# MCORD_MCX_SAS.net
KiCad netlist of a schematic drawn in Altium Designer
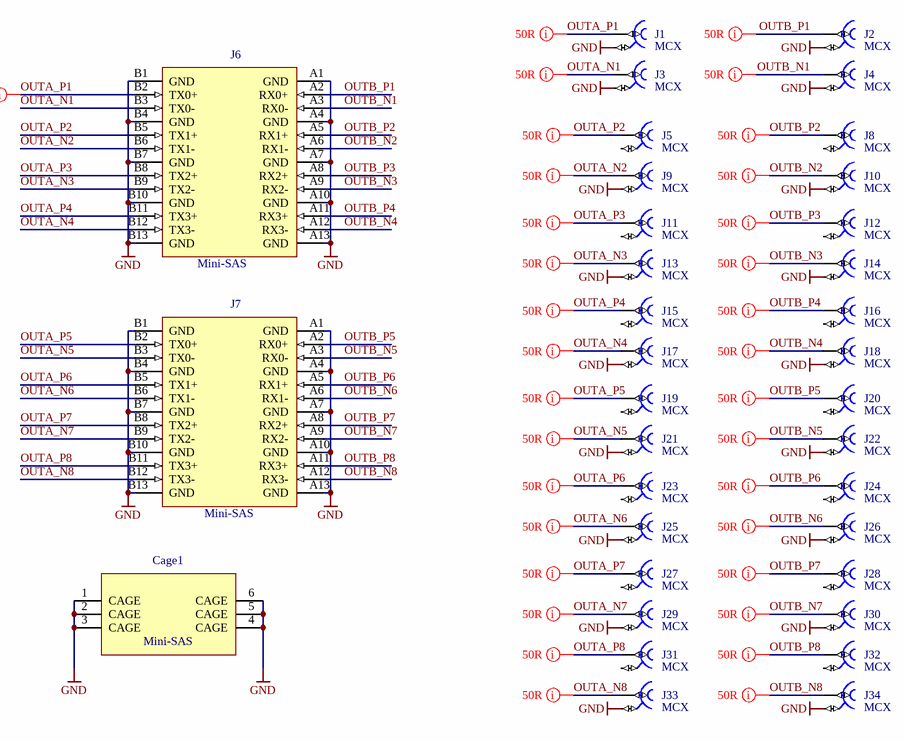
[diagram p0: MCORD_MCX_SAS.SchDoc]

(export (version "E")
  (design (tool "Eeschema 10.0.6"))
  (components
    (comp (ref "Cage1")
      (value "Mini-SAS")
      (footprint "TYCO_1888321-2")
      (description "Mini-SAS Cage (6Pins)")
      (fields
        (field (name "PART NUMBER") "TYCO_1888321-2")
        (field (name "MANUFACTURER") "TYCO ELECTRONICS")
        (field (name "AUTHOR") "CERN DEM BC")
      )
      (libsource (lib "Connectors") (part "Mini-SAS Cage (6Pins)"))
    )
    (comp (ref "J1")
      (value "MCX")
      (footprint "AMPHENOL_919-383J-51A")
      (fields
        (field (name "PART NUMBER") "AMPHENOL_919-383J-51A")
        (field (name "FAMILY") "MCX")
        (field (name "MANUFACTURER") "AMPHENOL")
        (field (name "MANUFACTURER PART NUMBER") "919-383J-51A")
        (field (name "AUTHOR") "CERN DEM BC")
      )
      (libsource (lib "Connectors") (part "Coax_1Female_1Shield"))
    )
    (comp (ref "J2")
      (value "MCX")
      (footprint "AMPHENOL_919-383J-51A")
      (fields
        (field (name "PART NUMBER") "AMPHENOL_919-383J-51A")
        (field (name "FAMILY") "MCX")
        (field (name "MANUFACTURER") "AMPHENOL")
        (field (name "MANUFACTURER PART NUMBER") "919-383J-51A")
        (field (name "AUTHOR") "CERN DEM BC")
      )
      (libsource (lib "Connectors") (part "Coax_1Female_1Shield"))
    )
    (comp (ref "J3")
      (value "MCX")
      (footprint "AMPHENOL_919-383J-51A")
      (fields
        (field (name "PART NUMBER") "AMPHENOL_919-383J-51A")
        (field (name "FAMILY") "MCX")
        (field (name "MANUFACTURER") "AMPHENOL")
        (field (name "MANUFACTURER PART NUMBER") "919-383J-51A")
        (field (name "AUTHOR") "CERN DEM BC")
      )
      (libsource (lib "Connectors") (part "Coax_1Female_1Shield"))
    )
    (comp (ref "J4")
      (value "MCX")
      (footprint "AMPHENOL_919-383J-51A")
      (fields
        (field (name "PART NUMBER") "AMPHENOL_919-383J-51A")
        (field (name "FAMILY") "MCX")
        (field (name "MANUFACTURER") "AMPHENOL")
        (field (name "MANUFACTURER PART NUMBER") "919-383J-51A")
        (field (name "AUTHOR") "CERN DEM BC")
      )
      (libsource (lib "Connectors") (part "Coax_1Female_1Shield"))
    )
    (comp (ref "J5")
      (value "MCX")
      (footprint "AMPHENOL_919-383J-51A")
      (fields
        (field (name "PART NUMBER") "AMPHENOL_919-383J-51A")
        (field (name "FAMILY") "MCX")
        (field (name "MANUFACTURER") "AMPHENOL")
        (field (name "MANUFACTURER PART NUMBER") "919-383J-51A")
        (field (name "AUTHOR") "CERN DEM BC")
      )
      (libsource (lib "Connectors") (part "Coax_1Female_1Shield"))
    )
    (comp (ref "J6")
      (value "Mini-SAS")
      (footprint "TYCO_1761987-7")
      (description "26 Position Mini-Sas Connector (Quad Small Form-Factor SFF-8088)")
      (fields
        (field (name "PART NUMBER") "TYCO_1761987-7")
        (field (name "MANUFACTURER") "TYCO ELECTRONICS")
        (field (name "AUTHOR") "CERN DEM MR")
      )
      (libsource (lib "Connectors") (part "Mini-SAS"))
    )
    (comp (ref "J7")
      (value "Mini-SAS")
      (footprint "TYCO_1761987-7")
      (description "26 Position Mini-Sas Connector (Quad Small Form-Factor SFF-8088)")
      (fields
        (field (name "PART NUMBER") "TYCO_1761987-7")
        (field (name "MANUFACTURER") "TYCO ELECTRONICS")
        (field (name "AUTHOR") "CERN DEM MR")
      )
      (libsource (lib "Connectors") (part "Mini-SAS"))
    )
    (comp (ref "J8")
      (value "MCX")
      (footprint "AMPHENOL_919-383J-51A")
      (fields
        (field (name "PART NUMBER") "AMPHENOL_919-383J-51A")
        (field (name "FAMILY") "MCX")
        (field (name "MANUFACTURER") "AMPHENOL")
        (field (name "MANUFACTURER PART NUMBER") "919-383J-51A")
        (field (name "AUTHOR") "CERN DEM BC")
      )
      (libsource (lib "Connectors") (part "Coax_1Female_1Shield"))
    )
    (comp (ref "J9")
      (value "MCX")
      (footprint "AMPHENOL_919-383J-51A")
      (fields
        (field (name "PART NUMBER") "AMPHENOL_919-383J-51A")
        (field (name "FAMILY") "MCX")
        (field (name "MANUFACTURER") "AMPHENOL")
        (field (name "MANUFACTURER PART NUMBER") "919-383J-51A")
        (field (name "AUTHOR") "CERN DEM BC")
      )
      (libsource (lib "Connectors") (part "Coax_1Female_1Shield"))
    )
    (comp (ref "J10")
      (value "MCX")
      (footprint "AMPHENOL_919-383J-51A")
      (fields
        (field (name "PART NUMBER") "AMPHENOL_919-383J-51A")
        (field (name "FAMILY") "MCX")
        (field (name "MANUFACTURER") "AMPHENOL")
        (field (name "MANUFACTURER PART NUMBER") "919-383J-51A")
        (field (name "AUTHOR") "CERN DEM BC")
      )
      (libsource (lib "Connectors") (part "Coax_1Female_1Shield"))
    )
    (comp (ref "J11")
      (value "MCX")
      (footprint "AMPHENOL_919-383J-51A")
      (fields
        (field (name "PART NUMBER") "AMPHENOL_919-383J-51A")
        (field (name "FAMILY") "MCX")
        (field (name "MANUFACTURER") "AMPHENOL")
        (field (name "MANUFACTURER PART NUMBER") "919-383J-51A")
        (field (name "AUTHOR") "CERN DEM BC")
      )
      (libsource (lib "Connectors") (part "Coax_1Female_1Shield"))
    )
    (comp (ref "J12")
      (value "MCX")
      (footprint "AMPHENOL_919-383J-51A")
      (fields
        (field (name "PART NUMBER") "AMPHENOL_919-383J-51A")
        (field (name "FAMILY") "MCX")
        (field (name "MANUFACTURER") "AMPHENOL")
        (field (name "MANUFACTURER PART NUMBER") "919-383J-51A")
        (field (name "AUTHOR") "CERN DEM BC")
      )
      (libsource (lib "Connectors") (part "Coax_1Female_1Shield"))
    )
    (comp (ref "J13")
      (value "MCX")
      (footprint "AMPHENOL_919-383J-51A")
      (fields
        (field (name "PART NUMBER") "AMPHENOL_919-383J-51A")
        (field (name "FAMILY") "MCX")
        (field (name "MANUFACTURER") "AMPHENOL")
        (field (name "MANUFACTURER PART NUMBER") "919-383J-51A")
        (field (name "AUTHOR") "CERN DEM BC")
      )
      (libsource (lib "Connectors") (part "Coax_1Female_1Shield"))
    )
    (comp (ref "J14")
      (value "MCX")
      (footprint "AMPHENOL_919-383J-51A")
      (fields
        (field (name "PART NUMBER") "AMPHENOL_919-383J-51A")
        (field (name "FAMILY") "MCX")
        (field (name "MANUFACTURER") "AMPHENOL")
        (field (name "MANUFACTURER PART NUMBER") "919-383J-51A")
        (field (name "AUTHOR") "CERN DEM BC")
      )
      (libsource (lib "Connectors") (part "Coax_1Female_1Shield"))
    )
    (comp (ref "J15")
      (value "MCX")
      (footprint "AMPHENOL_919-383J-51A")
      (fields
        (field (name "PART NUMBER") "AMPHENOL_919-383J-51A")
        (field (name "FAMILY") "MCX")
        (field (name "MANUFACTURER") "AMPHENOL")
        (field (name "MANUFACTURER PART NUMBER") "919-383J-51A")
        (field (name "AUTHOR") "CERN DEM BC")
      )
      (libsource (lib "Connectors") (part "Coax_1Female_1Shield"))
    )
    (comp (ref "J16")
      (value "MCX")
      (footprint "AMPHENOL_919-383J-51A")
      (fields
        (field (name "PART NUMBER") "AMPHENOL_919-383J-51A")
        (field (name "FAMILY") "MCX")
        (field (name "MANUFACTURER") "AMPHENOL")
        (field (name "MANUFACTURER PART NUMBER") "919-383J-51A")
        (field (name "AUTHOR") "CERN DEM BC")
      )
      (libsource (lib "Connectors") (part "Coax_1Female_1Shield"))
    )
    (comp (ref "J17")
      (value "MCX")
      (footprint "AMPHENOL_919-383J-51A")
      (fields
        (field (name "PART NUMBER") "AMPHENOL_919-383J-51A")
        (field (name "FAMILY") "MCX")
        (field (name "MANUFACTURER") "AMPHENOL")
        (field (name "MANUFACTURER PART NUMBER") "919-383J-51A")
        (field (name "AUTHOR") "CERN DEM BC")
      )
      (libsource (lib "Connectors") (part "Coax_1Female_1Shield"))
    )
    (comp (ref "J18")
      (value "MCX")
      (footprint "AMPHENOL_919-383J-51A")
      (fields
        (field (name "PART NUMBER") "AMPHENOL_919-383J-51A")
        (field (name "FAMILY") "MCX")
        (field (name "MANUFACTURER") "AMPHENOL")
        (field (name "MANUFACTURER PART NUMBER") "919-383J-51A")
        (field (name "AUTHOR") "CERN DEM BC")
      )
      (libsource (lib "Connectors") (part "Coax_1Female_1Shield"))
    )
    (comp (ref "J19")
      (value "MCX")
      (footprint "AMPHENOL_919-383J-51A")
      (fields
        (field (name "PART NUMBER") "AMPHENOL_919-383J-51A")
        (field (name "FAMILY") "MCX")
        (field (name "MANUFACTURER") "AMPHENOL")
        (field (name "MANUFACTURER PART NUMBER") "919-383J-51A")
        (field (name "AUTHOR") "CERN DEM BC")
      )
      (libsource (lib "Connectors") (part "Coax_1Female_1Shield"))
    )
    (comp (ref "J20")
      (value "MCX")
      (footprint "AMPHENOL_919-383J-51A")
      (fields
        (field (name "PART NUMBER") "AMPHENOL_919-383J-51A")
        (field (name "FAMILY") "MCX")
        (field (name "MANUFACTURER") "AMPHENOL")
        (field (name "MANUFACTURER PART NUMBER") "919-383J-51A")
        (field (name "AUTHOR") "CERN DEM BC")
      )
      (libsource (lib "Connectors") (part "Coax_1Female_1Shield"))
    )
    (comp (ref "J21")
      (value "MCX")
      (footprint "AMPHENOL_919-383J-51A")
      (fields
        (field (name "PART NUMBER") "AMPHENOL_919-383J-51A")
        (field (name "FAMILY") "MCX")
        (field (name "MANUFACTURER") "AMPHENOL")
        (field (name "MANUFACTURER PART NUMBER") "919-383J-51A")
        (field (name "AUTHOR") "CERN DEM BC")
      )
      (libsource (lib "Connectors") (part "Coax_1Female_1Shield"))
    )
    (comp (ref "J22")
      (value "MCX")
      (footprint "AMPHENOL_919-383J-51A")
      (fields
        (field (name "PART NUMBER") "AMPHENOL_919-383J-51A")
        (field (name "FAMILY") "MCX")
        (field (name "MANUFACTURER") "AMPHENOL")
        (field (name "MANUFACTURER PART NUMBER") "919-383J-51A")
        (field (name "AUTHOR") "CERN DEM BC")
      )
      (libsource (lib "Connectors") (part "Coax_1Female_1Shield"))
    )
    (comp (ref "J23")
      (value "MCX")
      (footprint "AMPHENOL_919-383J-51A")
      (fields
        (field (name "PART NUMBER") "AMPHENOL_919-383J-51A")
        (field (name "FAMILY") "MCX")
        (field (name "MANUFACTURER") "AMPHENOL")
        (field (name "MANUFACTURER PART NUMBER") "919-383J-51A")
        (field (name "AUTHOR") "CERN DEM BC")
      )
      (libsource (lib "Connectors") (part "Coax_1Female_1Shield"))
    )
    (comp (ref "J24")
      (value "MCX")
      (footprint "AMPHENOL_919-383J-51A")
      (fields
        (field (name "PART NUMBER") "AMPHENOL_919-383J-51A")
        (field (name "FAMILY") "MCX")
        (field (name "MANUFACTURER") "AMPHENOL")
        (field (name "MANUFACTURER PART NUMBER") "919-383J-51A")
        (field (name "AUTHOR") "CERN DEM BC")
      )
      (libsource (lib "Connectors") (part "Coax_1Female_1Shield"))
    )
    (comp (ref "J25")
      (value "MCX")
      (footprint "AMPHENOL_919-383J-51A")
      (fields
        (field (name "PART NUMBER") "AMPHENOL_919-383J-51A")
        (field (name "FAMILY") "MCX")
        (field (name "MANUFACTURER") "AMPHENOL")
        (field (name "MANUFACTURER PART NUMBER") "919-383J-51A")
        (field (name "AUTHOR") "CERN DEM BC")
      )
      (libsource (lib "Connectors") (part "Coax_1Female_1Shield"))
    )
    (comp (ref "J26")
      (value "MCX")
      (footprint "AMPHENOL_919-383J-51A")
      (fields
        (field (name "PART NUMBER") "AMPHENOL_919-383J-51A")
        (field (name "FAMILY") "MCX")
        (field (name "MANUFACTURER") "AMPHENOL")
        (field (name "MANUFACTURER PART NUMBER") "919-383J-51A")
        (field (name "AUTHOR") "CERN DEM BC")
      )
      (libsource (lib "Connectors") (part "Coax_1Female_1Shield"))
    )
    (comp (ref "J27")
      (value "MCX")
      (footprint "AMPHENOL_919-383J-51A")
      (fields
        (field (name "PART NUMBER") "AMPHENOL_919-383J-51A")
        (field (name "FAMILY") "MCX")
        (field (name "MANUFACTURER") "AMPHENOL")
        (field (name "MANUFACTURER PART NUMBER") "919-383J-51A")
        (field (name "AUTHOR") "CERN DEM BC")
      )
      (libsource (lib "Connectors") (part "Coax_1Female_1Shield"))
    )
    (comp (ref "J28")
      (value "MCX")
      (footprint "AMPHENOL_919-383J-51A")
      (fields
        (field (name "PART NUMBER") "AMPHENOL_919-383J-51A")
        (field (name "FAMILY") "MCX")
        (field (name "MANUFACTURER") "AMPHENOL")
        (field (name "MANUFACTURER PART NUMBER") "919-383J-51A")
        (field (name "AUTHOR") "CERN DEM BC")
      )
      (libsource (lib "Connectors") (part "Coax_1Female_1Shield"))
    )
    (comp (ref "J29")
      (value "MCX")
      (footprint "AMPHENOL_919-383J-51A")
      (fields
        (field (name "PART NUMBER") "AMPHENOL_919-383J-51A")
        (field (name "FAMILY") "MCX")
        (field (name "MANUFACTURER") "AMPHENOL")
        (field (name "MANUFACTURER PART NUMBER") "919-383J-51A")
        (field (name "AUTHOR") "CERN DEM BC")
      )
      (libsource (lib "Connectors") (part "Coax_1Female_1Shield"))
    )
    (comp (ref "J30")
      (value "MCX")
      (footprint "AMPHENOL_919-383J-51A")
      (fields
        (field (name "PART NUMBER") "AMPHENOL_919-383J-51A")
        (field (name "FAMILY") "MCX")
        (field (name "MANUFACTURER") "AMPHENOL")
        (field (name "MANUFACTURER PART NUMBER") "919-383J-51A")
        (field (name "AUTHOR") "CERN DEM BC")
      )
      (libsource (lib "Connectors") (part "Coax_1Female_1Shield"))
    )
    (comp (ref "J31")
      (value "MCX")
      (footprint "AMPHENOL_919-383J-51A")
      (fields
        (field (name "PART NUMBER") "AMPHENOL_919-383J-51A")
        (field (name "FAMILY") "MCX")
        (field (name "MANUFACTURER") "AMPHENOL")
        (field (name "MANUFACTURER PART NUMBER") "919-383J-51A")
        (field (name "AUTHOR") "CERN DEM BC")
      )
      (libsource (lib "Connectors") (part "Coax_1Female_1Shield"))
    )
    (comp (ref "J32")
      (value "MCX")
      (footprint "AMPHENOL_919-383J-51A")
      (fields
        (field (name "PART NUMBER") "AMPHENOL_919-383J-51A")
        (field (name "FAMILY") "MCX")
        (field (name "MANUFACTURER") "AMPHENOL")
        (field (name "MANUFACTURER PART NUMBER") "919-383J-51A")
        (field (name "AUTHOR") "CERN DEM BC")
      )
      (libsource (lib "Connectors") (part "Coax_1Female_1Shield"))
    )
    (comp (ref "J33")
      (value "MCX")
      (footprint "AMPHENOL_919-383J-51A")
      (fields
        (field (name "PART NUMBER") "AMPHENOL_919-383J-51A")
        (field (name "FAMILY") "MCX")
        (field (name "MANUFACTURER") "AMPHENOL")
        (field (name "MANUFACTURER PART NUMBER") "919-383J-51A")
        (field (name "AUTHOR") "CERN DEM BC")
      )
      (libsource (lib "Connectors") (part "Coax_1Female_1Shield"))
    )
    (comp (ref "J34")
      (value "MCX")
      (footprint "AMPHENOL_919-383J-51A")
      (fields
        (field (name "PART NUMBER") "AMPHENOL_919-383J-51A")
        (field (name "FAMILY") "MCX")
        (field (name "MANUFACTURER") "AMPHENOL")
        (field (name "MANUFACTURER PART NUMBER") "919-383J-51A")
        (field (name "AUTHOR") "CERN DEM BC")
      )
      (libsource (lib "Connectors") (part "Coax_1Female_1Shield"))
    )
  )
  (nets
    (net (code "1") (name "/OUTA_N1") (class "Default")
      (node (ref "J3") (pin "1") (pinfunction "1_1") (pintype "bidirectional"))
      (node (ref "J6") (pin "B3") (pinfunction "TX0-_B3") (pintype "input"))
    )
    (net (code "2") (name "/OUTA_N2") (class "Default")
      (node (ref "J6") (pin "B6") (pinfunction "TX1-_B6") (pintype "input"))
      (node (ref "J9") (pin "1") (pinfunction "1_1") (pintype "bidirectional"))
    )
    (net (code "3") (name "/OUTA_N3") (class "Default")
      (node (ref "J13") (pin "1") (pinfunction "1_1") (pintype "bidirectional"))
      (node (ref "J6") (pin "B9") (pinfunction "TX2-_B9") (pintype "input"))
    )
    (net (code "4") (name "/OUTA_N4") (class "Default")
      (node (ref "J17") (pin "1") (pinfunction "1_1") (pintype "bidirectional"))
      (node (ref "J6") (pin "B12") (pinfunction "TX3-_B12") (pintype "input"))
    )
    (net (code "5") (name "/OUTA_N5") (class "Default")
      (node (ref "J21") (pin "1") (pinfunction "1_1") (pintype "bidirectional"))
      (node (ref "J7") (pin "B3") (pinfunction "TX0-_B3") (pintype "input"))
    )
    (net (code "6") (name "/OUTA_N6") (class "Default")
      (node (ref "J25") (pin "1") (pinfunction "1_1") (pintype "bidirectional"))
      (node (ref "J7") (pin "B6") (pinfunction "TX1-_B6") (pintype "input"))
    )
    (net (code "7") (name "/OUTA_N7") (class "Default")
      (node (ref "J29") (pin "1") (pinfunction "1_1") (pintype "bidirectional"))
      (node (ref "J7") (pin "B9") (pinfunction "TX2-_B9") (pintype "input"))
    )
    (net (code "8") (name "/OUTA_N8") (class "Default")
      (node (ref "J33") (pin "1") (pinfunction "1_1") (pintype "bidirectional"))
      (node (ref "J7") (pin "B12") (pinfunction "TX3-_B12") (pintype "input"))
    )
    (net (code "9") (name "/OUTA_P1") (class "Default")
      (node (ref "J1") (pin "1") (pinfunction "1_1") (pintype "bidirectional"))
      (node (ref "J6") (pin "B2") (pinfunction "TX0+_B2") (pintype "input"))
    )
    (net (code "10") (name "/OUTA_P2") (class "Default")
      (node (ref "J5") (pin "1") (pinfunction "1_1") (pintype "bidirectional"))
      (node (ref "J6") (pin "B5") (pinfunction "TX1+_B5") (pintype "input"))
    )
    (net (code "11") (name "/OUTA_P3") (class "Default")
      (node (ref "J11") (pin "1") (pinfunction "1_1") (pintype "bidirectional"))
      (node (ref "J6") (pin "B8") (pinfunction "TX2+_B8") (pintype "input"))
    )
    (net (code "12") (name "/OUTA_P4") (class "Default")
      (node (ref "J15") (pin "1") (pinfunction "1_1") (pintype "bidirectional"))
      (node (ref "J6") (pin "B11") (pinfunction "TX3+_B11") (pintype "input"))
    )
    (net (code "13") (name "/OUTA_P5") (class "Default")
      (node (ref "J19") (pin "1") (pinfunction "1_1") (pintype "bidirectional"))
      (node (ref "J7") (pin "B2") (pinfunction "TX0+_B2") (pintype "input"))
    )
    (net (code "14") (name "/OUTA_P6") (class "Default")
      (node (ref "J23") (pin "1") (pinfunction "1_1") (pintype "bidirectional"))
      (node (ref "J7") (pin "B5") (pinfunction "TX1+_B5") (pintype "input"))
    )
    (net (code "15") (name "/OUTA_P7") (class "Default")
      (node (ref "J27") (pin "1") (pinfunction "1_1") (pintype "bidirectional"))
      (node (ref "J7") (pin "B8") (pinfunction "TX2+_B8") (pintype "input"))
    )
    (net (code "16") (name "/OUTA_P8") (class "Default")
      (node (ref "J31") (pin "1") (pinfunction "1_1") (pintype "bidirectional"))
      (node (ref "J7") (pin "B11") (pinfunction "TX3+_B11") (pintype "input"))
    )
    (net (code "17") (name "/OUTB_N1") (class "Default")
      (node (ref "J4") (pin "1") (pinfunction "1_1") (pintype "bidirectional"))
      (node (ref "J6") (pin "A3") (pinfunction "RX0-_A3") (pintype "input"))
    )
    (net (code "18") (name "/OUTB_N2") (class "Default")
      (node (ref "J10") (pin "1") (pinfunction "1_1") (pintype "bidirectional"))
      (node (ref "J6") (pin "A6") (pinfunction "RX1-_A6") (pintype "input"))
    )
    (net (code "19") (name "/OUTB_N3") (class "Default")
      (node (ref "J14") (pin "1") (pinfunction "1_1") (pintype "bidirectional"))
      (node (ref "J6") (pin "A9") (pinfunction "RX2-_A9") (pintype "input"))
    )
    (net (code "20") (name "/OUTB_N4") (class "Default")
      (node (ref "J18") (pin "1") (pinfunction "1_1") (pintype "bidirectional"))
      (node (ref "J6") (pin "A12") (pinfunction "RX3-_A12") (pintype "input"))
    )
    (net (code "21") (name "/OUTB_N5") (class "Default")
      (node (ref "J22") (pin "1") (pinfunction "1_1") (pintype "bidirectional"))
      (node (ref "J7") (pin "A3") (pinfunction "RX0-_A3") (pintype "input"))
    )
    (net (code "22") (name "/OUTB_N6") (class "Default")
      (node (ref "J26") (pin "1") (pinfunction "1_1") (pintype "bidirectional"))
      (node (ref "J7") (pin "A6") (pinfunction "RX1-_A6") (pintype "input"))
    )
    (net (code "23") (name "/OUTB_N7") (class "Default")
      (node (ref "J30") (pin "1") (pinfunction "1_1") (pintype "bidirectional"))
      (node (ref "J7") (pin "A9") (pinfunction "RX2-_A9") (pintype "input"))
    )
    (net (code "24") (name "/OUTB_N8") (class "Default")
      (node (ref "J34") (pin "1") (pinfunction "1_1") (pintype "bidirectional"))
      (node (ref "J7") (pin "A12") (pinfunction "RX3-_A12") (pintype "input"))
    )
    (net (code "25") (name "/OUTB_P1") (class "Default")
      (node (ref "J2") (pin "1") (pinfunction "1_1") (pintype "bidirectional"))
      (node (ref "J6") (pin "A2") (pinfunction "RX0+_A2") (pintype "input"))
    )
    (net (code "26") (name "/OUTB_P2") (class "Default")
      (node (ref "J6") (pin "A5") (pinfunction "RX1+_A5") (pintype "input"))
      (node (ref "J8") (pin "1") (pinfunction "1_1") (pintype "bidirectional"))
    )
    (net (code "27") (name "/OUTB_P3") (class "Default")
      (node (ref "J12") (pin "1") (pinfunction "1_1") (pintype "bidirectional"))
      (node (ref "J6") (pin "A8") (pinfunction "RX2+_A8") (pintype "input"))
    )
    (net (code "28") (name "/OUTB_P4") (class "Default")
      (node (ref "J16") (pin "1") (pinfunction "1_1") (pintype "bidirectional"))
      (node (ref "J6") (pin "A11") (pinfunction "RX3+_A11") (pintype "input"))
    )
    (net (code "29") (name "/OUTB_P5") (class "Default")
      (node (ref "J20") (pin "1") (pinfunction "1_1") (pintype "bidirectional"))
      (node (ref "J7") (pin "A2") (pinfunction "RX0+_A2") (pintype "input"))
    )
    (net (code "30") (name "/OUTB_P6") (class "Default")
      (node (ref "J24") (pin "1") (pinfunction "1_1") (pintype "bidirectional"))
      (node (ref "J7") (pin "A5") (pinfunction "RX1+_A5") (pintype "input"))
    )
    (net (code "31") (name "/OUTB_P7") (class "Default")
      (node (ref "J28") (pin "1") (pinfunction "1_1") (pintype "bidirectional"))
      (node (ref "J7") (pin "A8") (pinfunction "RX2+_A8") (pintype "input"))
    )
    (net (code "32") (name "/OUTB_P8") (class "Default")
      (node (ref "J32") (pin "1") (pinfunction "1_1") (pintype "bidirectional"))
      (node (ref "J7") (pin "A11") (pinfunction "RX3+_A11") (pintype "input"))
    )
    (net (code "33") (name "GND") (class "Default")
      (node (ref "Cage1") (pin "1") (pinfunction "CAGE_1") (pintype "power_in"))
      (node (ref "Cage1") (pin "2") (pinfunction "CAGE_2") (pintype "power_in"))
      (node (ref "Cage1") (pin "3") (pinfunction "CAGE_3") (pintype "power_in"))
      (node (ref "Cage1") (pin "4") (pinfunction "CAGE_4") (pintype "power_in"))
      (node (ref "Cage1") (pin "5") (pinfunction "CAGE_5") (pintype "power_in"))
      (node (ref "Cage1") (pin "6") (pinfunction "CAGE_6") (pintype "power_in"))
      (node (ref "J1") (pin "2") (pinfunction "2_2") (pintype "bidirectional"))
      (node (ref "J10") (pin "2") (pinfunction "2_2") (pintype "bidirectional"))
      (node (ref "J13") (pin "2") (pinfunction "2_2") (pintype "bidirectional"))
      (node (ref "J14") (pin "2") (pinfunction "2_2") (pintype "bidirectional"))
      (node (ref "J17") (pin "2") (pinfunction "2_2") (pintype "bidirectional"))
      (node (ref "J18") (pin "2") (pinfunction "2_2") (pintype "bidirectional"))
      (node (ref "J2") (pin "2") (pinfunction "2_2") (pintype "bidirectional"))
      (node (ref "J21") (pin "2") (pinfunction "2_2") (pintype "bidirectional"))
      (node (ref "J22") (pin "2") (pinfunction "2_2") (pintype "bidirectional"))
      (node (ref "J25") (pin "2") (pinfunction "2_2") (pintype "bidirectional"))
      (node (ref "J26") (pin "2") (pinfunction "2_2") (pintype "bidirectional"))
      (node (ref "J29") (pin "2") (pinfunction "2_2") (pintype "bidirectional"))
      (node (ref "J3") (pin "2") (pinfunction "2_2") (pintype "bidirectional"))
      (node (ref "J30") (pin "2") (pinfunction "2_2") (pintype "bidirectional"))
      (node (ref "J33") (pin "2") (pinfunction "2_2") (pintype "bidirectional"))
      (node (ref "J34") (pin "2") (pinfunction "2_2") (pintype "bidirectional"))
      (node (ref "J4") (pin "2") (pinfunction "2_2") (pintype "bidirectional"))
      (node (ref "J6") (pin "A1") (pinfunction "GND_A1") (pintype "power_in"))
      (node (ref "J6") (pin "A10") (pinfunction "GND_A10") (pintype "power_in"))
      (node (ref "J6") (pin "A13") (pinfunction "GND_A13") (pintype "power_in"))
      (node (ref "J6") (pin "A4") (pinfunction "GND_A4") (pintype "power_in"))
      (node (ref "J6") (pin "A7") (pinfunction "GND_A7") (pintype "power_in"))
      (node (ref "J6") (pin "B1") (pinfunction "GND_B1") (pintype "power_in"))
      (node (ref "J6") (pin "B10") (pinfunction "GND_B10") (pintype "power_in"))
      (node (ref "J6") (pin "B13") (pinfunction "GND_B13") (pintype "power_in"))
      (node (ref "J6") (pin "B4") (pinfunction "GND_B4") (pintype "power_in"))
      (node (ref "J6") (pin "B7") (pinfunction "GND_B7") (pintype "power_in"))
      (node (ref "J7") (pin "A1") (pinfunction "GND_A1") (pintype "power_in"))
      (node (ref "J7") (pin "A10") (pinfunction "GND_A10") (pintype "power_in"))
      (node (ref "J7") (pin "A13") (pinfunction "GND_A13") (pintype "power_in"))
      (node (ref "J7") (pin "A4") (pinfunction "GND_A4") (pintype "power_in"))
      (node (ref "J7") (pin "A7") (pinfunction "GND_A7") (pintype "power_in"))
      (node (ref "J7") (pin "B1") (pinfunction "GND_B1") (pintype "power_in"))
      (node (ref "J7") (pin "B10") (pinfunction "GND_B10") (pintype "power_in"))
      (node (ref "J7") (pin "B13") (pinfunction "GND_B13") (pintype "power_in"))
      (node (ref "J7") (pin "B4") (pinfunction "GND_B4") (pintype "power_in"))
      (node (ref "J7") (pin "B7") (pinfunction "GND_B7") (pintype "power_in"))
      (node (ref "J9") (pin "2") (pinfunction "2_2") (pintype "bidirectional"))
    )
    (net (code "34") (name "unconnected-(J5-Pad2)") (class "Default")
      (node (ref "J5") (pin "2") (pinfunction "2_2") (pintype "bidirectional"))
    )
    (net (code "35") (name "unconnected-(J8-Pad2)") (class "Default")
      (node (ref "J8") (pin "2") (pinfunction "2_2") (pintype "bidirectional"))
    )
    (net (code "36") (name "unconnected-(J11-Pad2)") (class "Default")
      (node (ref "J11") (pin "2") (pinfunction "2_2") (pintype "bidirectional"))
    )
    (net (code "37") (name "unconnected-(J12-Pad2)") (class "Default")
      (node (ref "J12") (pin "2") (pinfunction "2_2") (pintype "bidirectional"))
    )
    (net (code "38") (name "unconnected-(J15-Pad2)") (class "Default")
      (node (ref "J15") (pin "2") (pinfunction "2_2") (pintype "bidirectional"))
    )
    (net (code "39") (name "unconnected-(J16-Pad2)") (class "Default")
      (node (ref "J16") (pin "2") (pinfunction "2_2") (pintype "bidirectional"))
    )
    (net (code "40") (name "unconnected-(J19-Pad2)") (class "Default")
      (node (ref "J19") (pin "2") (pinfunction "2_2") (pintype "bidirectional"))
    )
    (net (code "41") (name "unconnected-(J20-Pad2)") (class "Default")
      (node (ref "J20") (pin "2") (pinfunction "2_2") (pintype "bidirectional"))
    )
    (net (code "42") (name "unconnected-(J23-Pad2)") (class "Default")
      (node (ref "J23") (pin "2") (pinfunction "2_2") (pintype "bidirectional"))
    )
    (net (code "43") (name "unconnected-(J24-Pad2)") (class "Default")
      (node (ref "J24") (pin "2") (pinfunction "2_2") (pintype "bidirectional"))
    )
    (net (code "44") (name "unconnected-(J27-Pad2)") (class "Default")
      (node (ref "J27") (pin "2") (pinfunction "2_2") (pintype "bidirectional"))
    )
    (net (code "45") (name "unconnected-(J28-Pad2)") (class "Default")
      (node (ref "J28") (pin "2") (pinfunction "2_2") (pintype "bidirectional"))
    )
    (net (code "46") (name "unconnected-(J31-Pad2)") (class "Default")
      (node (ref "J31") (pin "2") (pinfunction "2_2") (pintype "bidirectional"))
    )
    (net (code "47") (name "unconnected-(J32-Pad2)") (class "Default")
      (node (ref "J32") (pin "2") (pinfunction "2_2") (pintype "bidirectional"))
    )
  )
)
